# USB_Type-C.net
KiCad netlist of a schematic drawn in Altium Designer
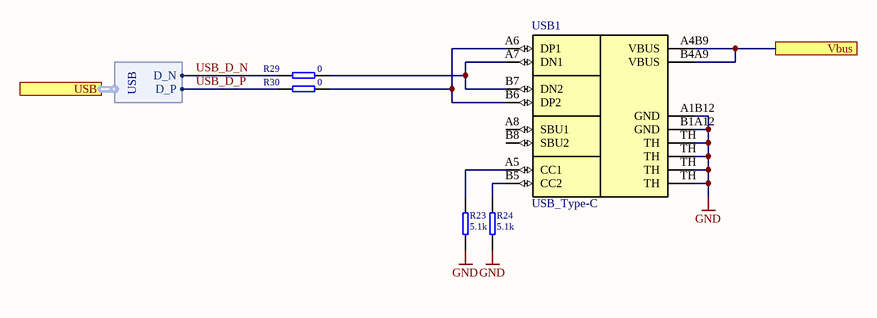
[diagram p0: USB_Type-C.SchDoc]

(export (version "E")
  (design (tool "Eeschema 10.0.6"))
  (components
    (comp (ref "R23")
      (value "5.1k")
      (footprint "RES 0402")
      (description "Resistor")
      (fields (field (name "Comment") "RES 0402 5.1k"))
      (libsource (lib "!main") (part "!Resistor"))
    )
    (comp (ref "R24")
      (value "5.1k")
      (footprint "RES 0402")
      (description "Resistor")
      (fields (field (name "Comment") "RES 0402 5.1k"))
      (libsource (lib "!main") (part "!Resistor"))
    )
    (comp (ref "R29")
      (value "0")
      (footprint "RES 0402")
      (description "Resistor")
      (fields (field (name "Comment") "RES 0402 0"))
      (libsource (lib "!main") (part "!Resistor"))
    )
    (comp (ref "R30")
      (value "0")
      (footprint "RES 0402")
      (description "Resistor")
      (fields (field (name "Comment") "RES 0402 0"))
      (libsource (lib "!main") (part "!Resistor"))
    )
    (comp (ref "USB1")
      (value "USB_Type-C")
      (footprint "USB_Type-C")
      (description "USB Type-C connector")
      (libsource (lib "connectors") (part "USB_Type-C"))
    )
  )
  (nets
    (net (code "2") (name "/USB_D_N") (class "Default")
      (node (ref "R29") (pin "1") (pinfunction "11_1") (pintype "passive"))
    )
    (net (code "3") (name "/USB_D_P") (class "Default")
      (node (ref "R30") (pin "1") (pinfunction "11_1") (pintype "passive"))
    )
    (net (code "4") (name "/Vbus") (class "Default")
      (node (ref "USB1") (pin "A4B9") (pinfunction "VBUS_A4B9") (pintype "power_in"))
      (node (ref "USB1") (pin "B4A9") (pinfunction "VBUS_B4A9") (pintype "power_in"))
    )
    (net (code "6") (name "GND") (class "Default")
      (node (ref "R23") (pin "1") (pinfunction "11_1") (pintype "passive"))
      (node (ref "R24") (pin "1") (pinfunction "11_1") (pintype "passive"))
      (node (ref "USB1") (pin "A1B12") (pinfunction "GND_A1B12") (pintype "power_in"))
      (node (ref "USB1") (pin "B1A12") (pinfunction "GND_B1A12") (pintype "power_in"))
      (node (ref "USB1") (pin "TH") (pinfunction "TH_TH") (pintype "passive"))
    )
    (net (code "7") (name "Net-(R23-12)") (class "Default")
      (node (ref "R23") (pin "2") (pinfunction "12_2") (pintype "passive"))
      (node (ref "USB1") (pin "A5") (pinfunction "CC1_A5") (pintype "bidirectional"))
    )
    (net (code "8") (name "Net-(R24-12)") (class "Default")
      (node (ref "R24") (pin "2") (pinfunction "12_2") (pintype "passive"))
      (node (ref "USB1") (pin "B5") (pinfunction "CC2_B5") (pintype "bidirectional"))
    )
    (net (code "9") (name "Net-(R29-12)") (class "Default")
      (node (ref "R29") (pin "2") (pinfunction "12_2") (pintype "passive"))
      (node (ref "USB1") (pin "A7") (pinfunction "DN1_A7") (pintype "bidirectional"))
      (node (ref "USB1") (pin "B7") (pinfunction "DN2_B7") (pintype "bidirectional"))
    )
    (net (code "10") (name "Net-(R30-12)") (class "Default")
      (node (ref "R30") (pin "2") (pinfunction "12_2") (pintype "passive"))
      (node (ref "USB1") (pin "A6") (pinfunction "DP1_A6") (pintype "bidirectional"))
      (node (ref "USB1") (pin "B6") (pinfunction "DP2_B6") (pintype "bidirectional"))
    )
    (net (code "11") (name "unconnected-(USB1-SBU1-PadA8)") (class "Default")
      (node (ref "USB1") (pin "A8") (pinfunction "SBU1_A8") (pintype "bidirectional"))
    )
    (net (code "12") (name "unconnected-(USB1-SBU2-PadB8)") (class "Default")
      (node (ref "USB1") (pin "B8") (pinfunction "SBU2_B8") (pintype "bidirectional"))
    )
  )
)
